# aufsatz_v2_1_usb.net
KiCad netlist of a schematic drawn in EAGLE
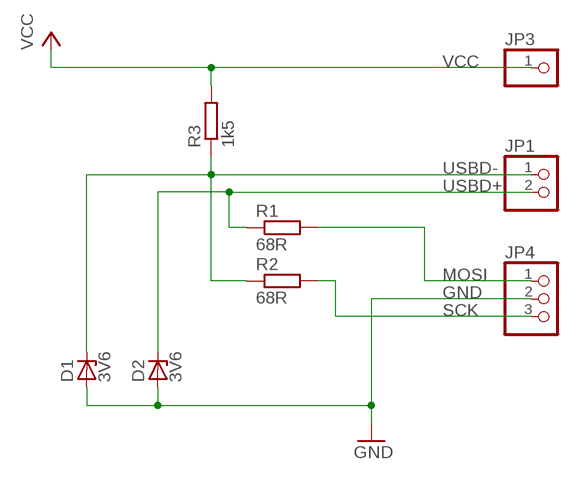
[diagram p0: schematic, sheet 1]

(export (version "E")
  (design (tool "Eeschema 10.0.6"))
  (components
    (comp (ref "D1")
      (value "3V6")
      (footprint "eagle-import:SOD80C")
      (libsource (lib "eagle-import") (part "ZENER-DIODESOD80C"))
    )
    (comp (ref "D2")
      (value "3V6")
      (footprint "eagle-import:SOD80C")
      (libsource (lib "eagle-import") (part "ZENER-DIODESOD80C"))
    )
    (comp (ref "JP1")
      (value "PINHD-1X2")
      (footprint "eagle-import:1X02")
      (libsource (lib "eagle-import") (part "PINHD-1X2"))
    )
    (comp (ref "JP3")
      (value "PINHD-1X1")
      (footprint "eagle-import:1X01")
      (libsource (lib "eagle-import") (part "PINHD-1X1"))
    )
    (comp (ref "JP4")
      (value "PINHD-1X3")
      (footprint "eagle-import:1X03")
      (libsource (lib "eagle-import") (part "PINHD-1X3"))
    )
    (comp (ref "R1")
      (value "68R")
      (footprint "eagle-import:R0805")
      (libsource (lib "eagle-import") (part "R-EU_R0805"))
    )
    (comp (ref "R2")
      (value "68R")
      (footprint "eagle-import:R0805")
      (libsource (lib "eagle-import") (part "R-EU_R0805"))
    )
    (comp (ref "R3")
      (value "1k5")
      (footprint "eagle-import:R0805")
      (libsource (lib "eagle-import") (part "R-EU_R0805"))
    )
  )
  (nets
    (net (code "1") (name "/MOSI") (class "Default")
      (node (ref "JP4") (pin "1") (pinfunction "1_1") (pintype "passive"))
      (node (ref "R1") (pin "2") (pinfunction "2_2") (pintype "passive"))
    )
    (net (code "2") (name "/SCK") (class "Default")
      (node (ref "JP4") (pin "3") (pinfunction "3_3") (pintype "passive"))
      (node (ref "R2") (pin "2") (pinfunction "2_2") (pintype "passive"))
    )
    (net (code "3") (name "/USBD+") (class "Default")
      (node (ref "D2") (pin "C") (pinfunction "C_C") (pintype "passive"))
      (node (ref "JP1") (pin "2") (pinfunction "2_2") (pintype "passive"))
      (node (ref "R1") (pin "1") (pinfunction "1_1") (pintype "passive"))
    )
    (net (code "4") (name "/USBD-") (class "Default")
      (node (ref "D1") (pin "C") (pinfunction "C_C") (pintype "passive"))
      (node (ref "JP1") (pin "1") (pinfunction "1_1") (pintype "passive"))
      (node (ref "R2") (pin "1") (pinfunction "1_1") (pintype "passive"))
      (node (ref "R3") (pin "1") (pinfunction "1_1") (pintype "passive"))
    )
    (net (code "5") (name "GND") (class "Default")
      (node (ref "D1") (pin "A") (pinfunction "A_A") (pintype "passive"))
      (node (ref "D2") (pin "A") (pinfunction "A_A") (pintype "passive"))
      (node (ref "JP4") (pin "2") (pinfunction "2_2") (pintype "passive"))
    )
    (net (code "6") (name "VCC") (class "Default")
      (node (ref "JP3") (pin "1") (pinfunction "1_1") (pintype "passive"))
      (node (ref "R3") (pin "2") (pinfunction "2_2") (pintype "passive"))
    )
  )
)
